# SparkFunLilyPixel.net
KiCad netlist of a schematic drawn in EAGLE
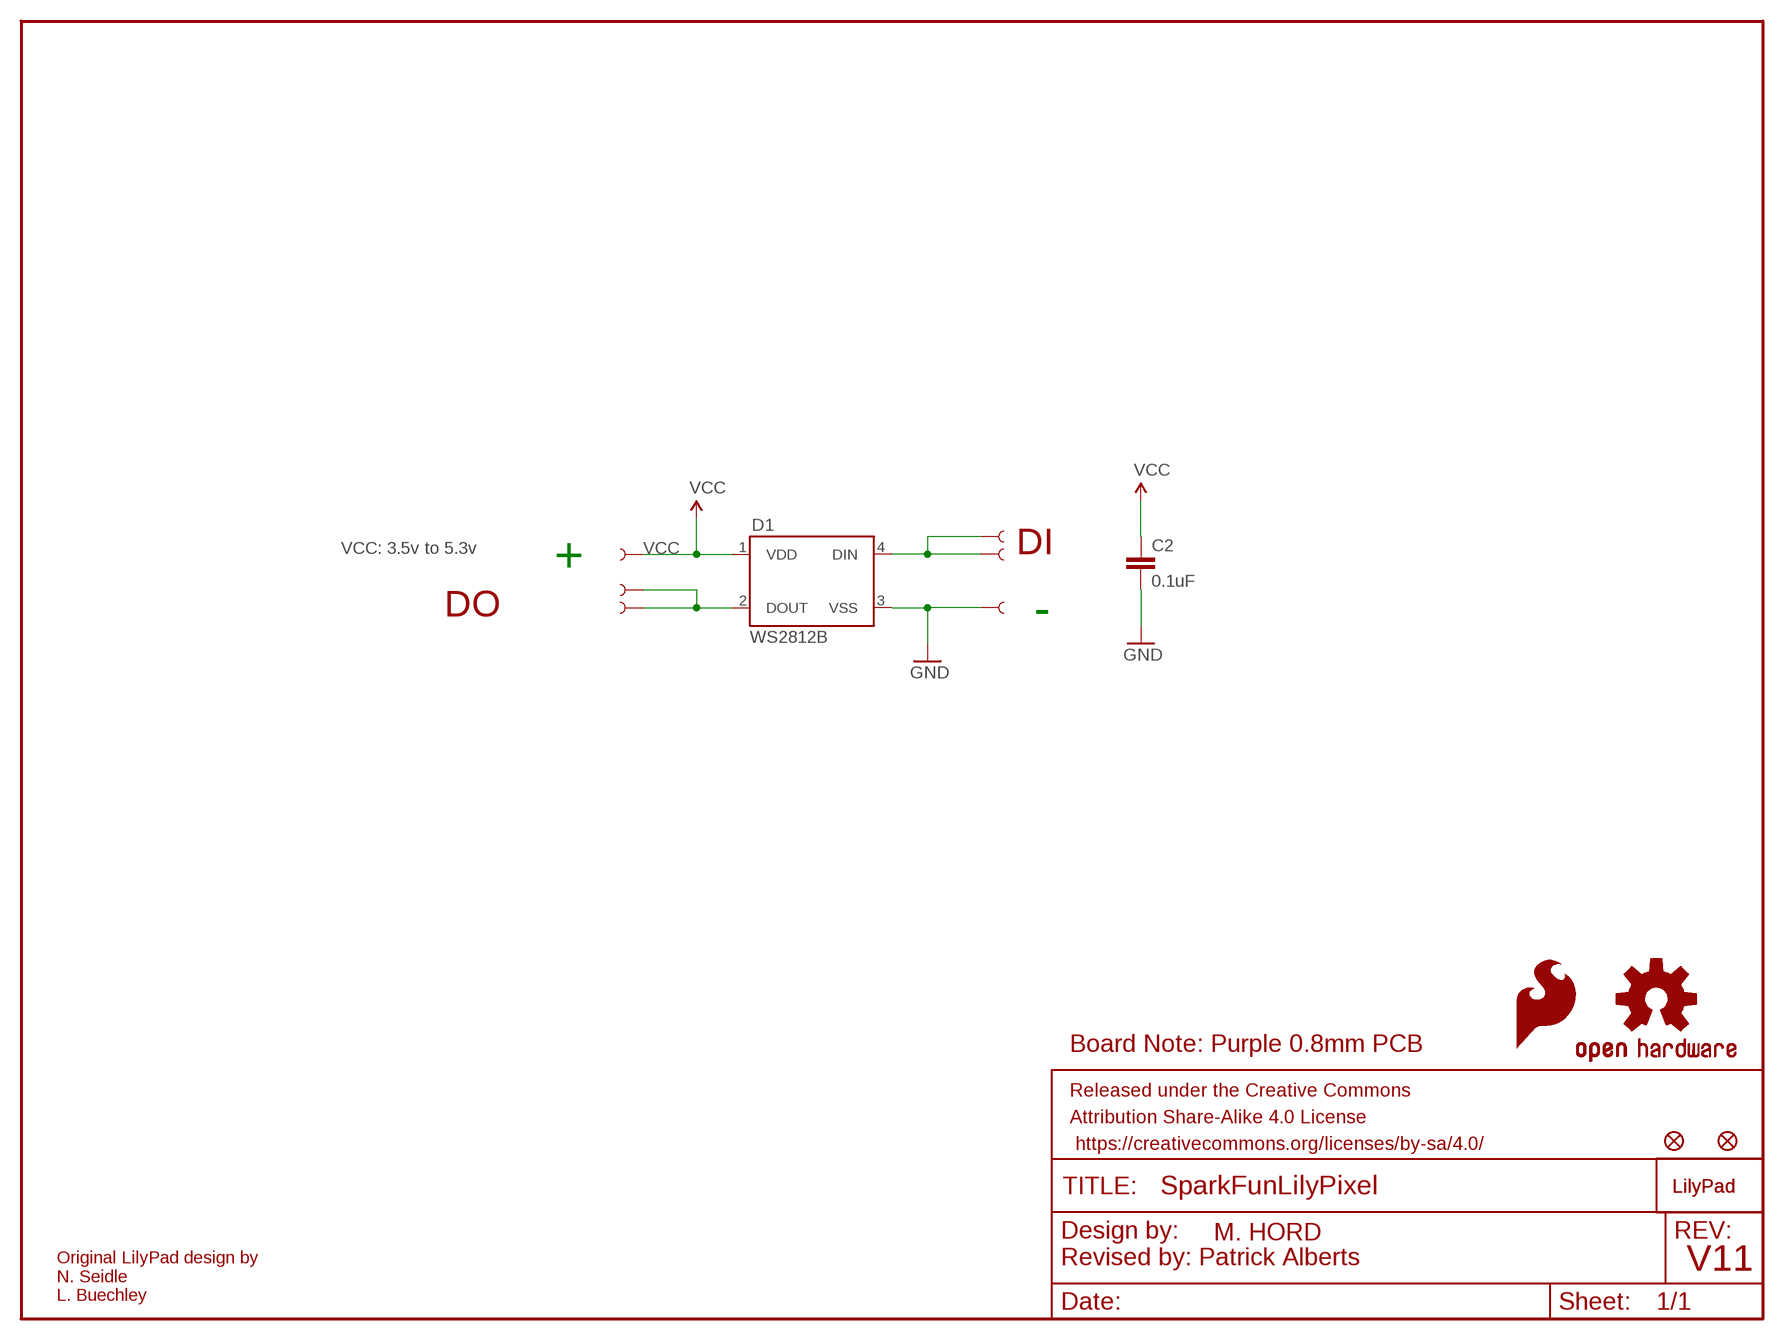
[diagram p0: schematic, sheet 1]

(export (version "E")
  (design (tool "Eeschema 10.0.6"))
  (components
    (comp (ref "C2")
      (value "0.1uF")
      (footprint "eagle-import:0603-CAP")
      (libsource (lib "eagle-import") (part "0.1UF-25V(+80/-20%)(0603)"))
    )
    (comp (ref "D1")
      (value "WS2812B")
      (footprint "eagle-import:WS2812B")
      (libsource (lib "eagle-import") (part "WS2812B"))
    )
    (comp (ref "FID1")
      (value "FIDUCIAL1X2")
      (footprint "eagle-import:FIDUCIAL-1X2")
      (libsource (lib "eagle-import") (part "FIDUCIAL1X2"))
    )
    (comp (ref "FID2")
      (value "FIDUCIAL1X2")
      (footprint "eagle-import:FIDUCIAL-1X2")
      (libsource (lib "eagle-import") (part "FIDUCIAL1X2"))
    )
    (comp (ref "FRAME1")
      (value "FRAME-LETTER")
      (footprint "eagle-import:CREATIVE_COMMONS")
      (libsource (lib "eagle-import") (part "FRAME-LETTER"))
    )
    (comp (ref "JP1")
      (value "SEWTAP6")
      (footprint "eagle-import:PETAL-SMALL-2SIDE")
      (libsource (lib "eagle-import") (part "SEWTAP6"))
    )
    (comp (ref "JP2")
      (value "SEWTAP6")
      (footprint "eagle-import:PETAL-SMALL-2SIDE")
      (libsource (lib "eagle-import") (part "SEWTAP6"))
    )
    (comp (ref "JP3")
      (value "SEWTAP6")
      (footprint "eagle-import:PETAL-SMALL-2SIDE")
      (libsource (lib "eagle-import") (part "SEWTAP6"))
    )
    (comp (ref "JP4")
      (value "SEWTAP6")
      (footprint "eagle-import:PETAL-SMALL-2SIDE")
      (libsource (lib "eagle-import") (part "SEWTAP6"))
    )
    (comp (ref "JP5")
      (value "SEWTAP6")
      (footprint "eagle-import:PETAL-SMALL-2SIDE")
      (libsource (lib "eagle-import") (part "SEWTAP6"))
    )
    (comp (ref "JP6")
      (value "SEWTAP6")
      (footprint "eagle-import:PETAL-SMALL-2SIDE")
      (libsource (lib "eagle-import") (part "SEWTAP6"))
    )
    (comp (ref "LOGO1")
      (value "OSHW-LOGOS")
      (footprint "eagle-import:OSHW-LOGO-S")
      (libsource (lib "eagle-import") (part "OSHW-LOGOS"))
    )
    (comp (ref "LOGO2")
      (value "SFE_LOGO_FLAME.1_INCH")
      (footprint "eagle-import:SFE_LOGO_FLAME_.1")
      (libsource (lib "eagle-import") (part "SFE_LOGO_FLAME.1_INCH"))
    )
    (comp (ref "U$1")
      (value "LOGO-LPLP")
      (footprint "eagle-import:LOGO-LILYPAD")
      (libsource (lib "eagle-import") (part "LOGO-LPLP"))
    )
    (comp (ref "U$8")
      (value "LOGO-LPL")
      (footprint "eagle-import:LOGO-L")
      (libsource (lib "eagle-import") (part "LOGO-LPL"))
    )
  )
  (nets
    (net (code "1") (name "GND") (class "Default")
      (node (ref "C2") (pin "2") (pinfunction "2_2") (pintype "passive"))
      (node (ref "D1") (pin "3") (pinfunction "VSS_3") (pintype "power_in"))
      (node (ref "JP3") (pin "1") (pinfunction "1_1") (pintype "bidirectional"))
    )
    (net (code "2") (name "Net-(D1-DIN)") (class "Default")
      (node (ref "D1") (pin "4") (pinfunction "DIN_4") (pintype "input"))
      (node (ref "JP5") (pin "1") (pinfunction "1_1") (pintype "bidirectional"))
      (node (ref "JP6") (pin "1") (pinfunction "1_1") (pintype "bidirectional"))
    )
    (net (code "3") (name "Net-(D1-DOUT)") (class "Default")
      (node (ref "D1") (pin "2") (pinfunction "DOUT_2") (pintype "output"))
      (node (ref "JP1") (pin "1") (pinfunction "1_1") (pintype "bidirectional"))
      (node (ref "JP2") (pin "1") (pinfunction "1_1") (pintype "bidirectional"))
    )
    (net (code "4") (name "VCC") (class "Default")
      (node (ref "C2") (pin "1") (pinfunction "1_1") (pintype "passive"))
      (node (ref "D1") (pin "1") (pinfunction "VDD_1") (pintype "power_in"))
      (node (ref "JP4") (pin "1") (pinfunction "1_1") (pintype "bidirectional"))
    )
  )
)
